# PWM_Generator.net
KiCad netlist of a schematic drawn in Altium Designer
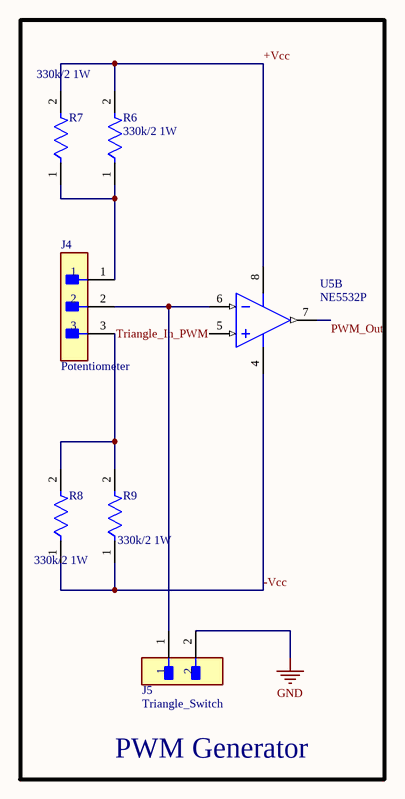
[diagram p0: PWM_Generator.SchDoc]

(export (version "E")
  (design (tool "Eeschema 10.0.6"))
  (components
    (comp (ref "J4")
      (value "Potentiometer")
      (footprint "FP-440054-3-MFG")
      (description "CONN HEADER VERT 3POS 2MM")
      (fields
        (field (name "OCTOPART") "https://octopart.com/440054-3-te+connectivity-40394845")
        (field (name "MANUFACTURER") "TE Connectivity")
      )
      (libsource (lib "Altium Content Vault") (part "0d3f023dd272f625e17a2be33dea85f"))
    )
    (comp (ref "J5")
      (value "Triangle_Switch")
      (footprint "FP-B2B-XH-A_LF_SN-MFG")
      (description "CONN HEADER VERT 2POS 2.5MM")
      (libsource (lib "Altium Content Vault") (part "3bc925449376181038e59eaffc5286c"))
    )
    (comp (ref "R6")
      (value "330k/2 1W")
      (footprint "FP-RR01-MFG")
      (description "RES 100K OHM 5% 1W AXIAL")
      (fields (field (name "TOLERANCE") "5%"))
      (libsource (lib "Altium Content Vault") (part "1029c3af85768c4190bb7ad29bc67b5"))
    )
    (comp (ref "R7")
      (value "330k/2 1W")
      (footprint "FP-RR01-MFG")
      (description "RES 100K OHM 5% 1W AXIAL")
      (fields (field (name "TOLERANCE") "5%"))
      (libsource (lib "Altium Content Vault") (part "1029c3af85768c4190bb7ad29bc67b5"))
    )
    (comp (ref "R8")
      (value "330k/2 1W")
      (footprint "FP-RR01-MFG")
      (description "RES 100K OHM 5% 1W AXIAL")
      (fields (field (name "TOLERANCE") "5%"))
      (libsource (lib "Altium Content Vault") (part "1029c3af85768c4190bb7ad29bc67b5"))
    )
    (comp (ref "R9")
      (value "330k/2 1W")
      (footprint "FP-RR01-MFG")
      (description "RES 100K OHM 5% 1W AXIAL")
      (fields (field (name "TOLERANCE") "5%"))
      (libsource (lib "Altium Content Vault") (part "1029c3af85768c4190bb7ad29bc67b5"))
    )
    (comp (ref "U5")
      (value "NE5532P")
      (footprint "P0008A")
      (fields (field (name "MANUFACTURER") "Texas Instruments"))
      (libsource (lib "Altium Content Vault") (part "TI-AMP-D6-2-8_D"))
    )
  )
  (nets
    (net (code "1") (name "/+Vcc") (class "Default")
      (node (ref "R6") (pin "2") (pinfunction "2_2") (pintype "passive"))
      (node (ref "R7") (pin "2") (pinfunction "2_2") (pintype "passive"))
      (node (ref "U5") (pin "8") (pinfunction "VCC+_8") (pintype "power_in"))
    )
    (net (code "2") (name "/-Vcc") (class "Default")
      (node (ref "R8") (pin "1") (pinfunction "1_1") (pintype "passive"))
      (node (ref "R9") (pin "1") (pinfunction "1_1") (pintype "passive"))
      (node (ref "U5") (pin "4") (pinfunction "VCC-_4") (pintype "power_in"))
    )
    (net (code "3") (name "/PWM_Out") (class "Default")
      (node (ref "U5") (pin "7") (pinfunction "OUT2_7") (pintype "output"))
    )
    (net (code "4") (name "/Triangle_In_PWM") (class "Default")
      (node (ref "U5") (pin "5") (pinfunction "IN2+_5") (pintype "input"))
    )
    (net (code "5") (name "GND") (class "Default")
      (node (ref "J5") (pin "2") (pinfunction "2_2") (pintype "passive"))
    )
    (net (code "6") (name "Net-(J4-Pad1)") (class "Default")
      (node (ref "J4") (pin "1") (pinfunction "1_1") (pintype "passive"))
      (node (ref "R6") (pin "1") (pinfunction "1_1") (pintype "passive"))
      (node (ref "R7") (pin "1") (pinfunction "1_1") (pintype "passive"))
    )
    (net (code "7") (name "Net-(J4-Pad3)") (class "Default")
      (node (ref "J4") (pin "3") (pinfunction "3_3") (pintype "passive"))
      (node (ref "R8") (pin "2") (pinfunction "2_2") (pintype "passive"))
      (node (ref "R9") (pin "2") (pinfunction "2_2") (pintype "passive"))
    )
    (net (code "8") (name "Net-(U5B-IN2-)") (class "Default")
      (node (ref "J4") (pin "2") (pinfunction "2_2") (pintype "passive"))
      (node (ref "J5") (pin "1") (pinfunction "1_1") (pintype "passive"))
      (node (ref "U5") (pin "6") (pinfunction "IN2-_6") (pintype "input"))
    )
  )
)
